# Relay8WatchdogShield.net
KiCad netlist of a schematic drawn in EAGLE
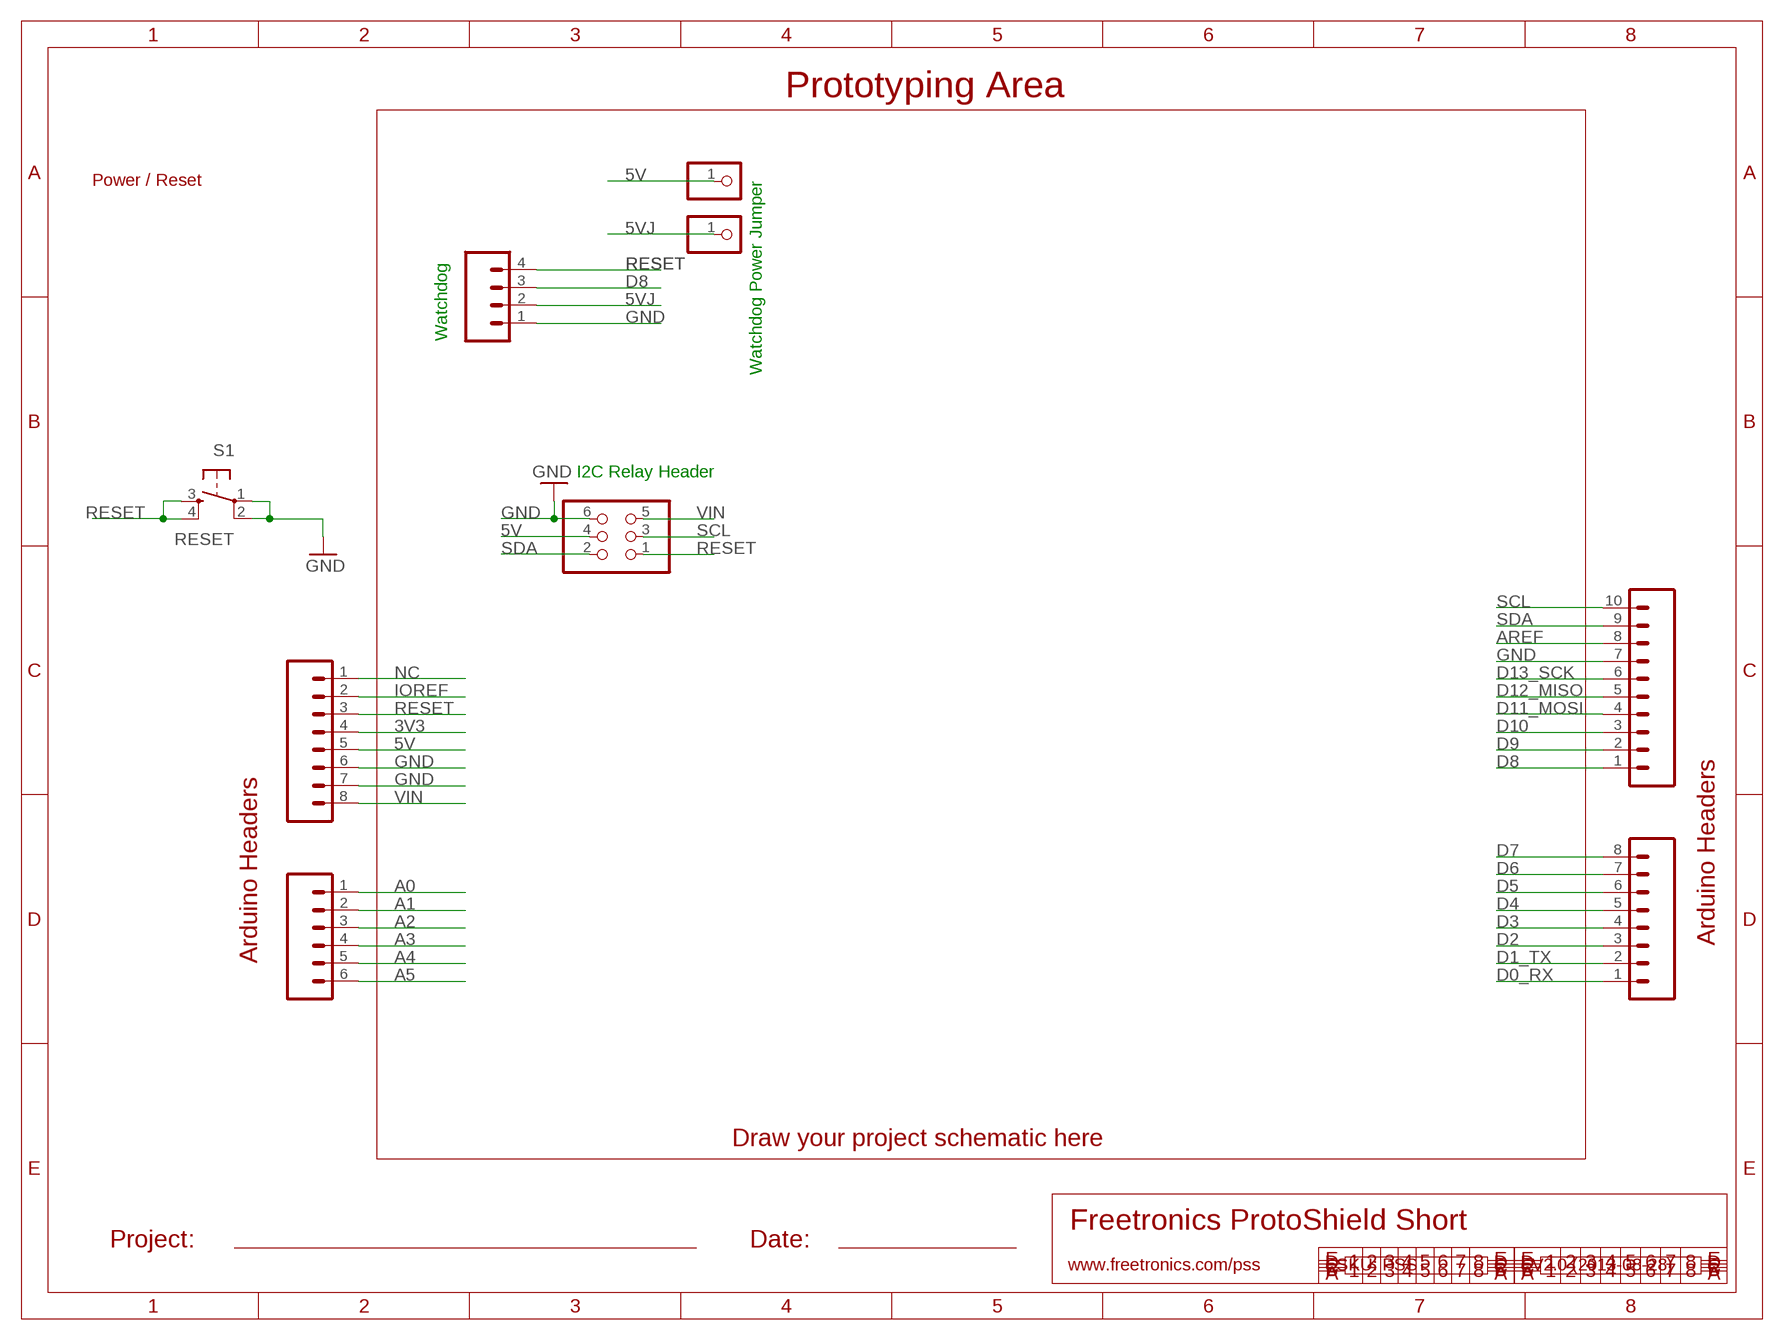
[diagram p0: schematic, sheet 1]

(export (version "E")
  (design (tool "Eeschema 10.0.6"))
  (components
    (comp (ref "J1")
      (value "Digital_0_7")
      (footprint "eagle-import:1X08")
      (libsource (lib "eagle-import") (part "M08"))
    )
    (comp (ref "J2")
      (value "Analog")
      (footprint "eagle-import:1X06")
      (libsource (lib "eagle-import") (part "M06SIP"))
    )
    (comp (ref "J3")
      (value "Digital_8_13")
      (footprint "eagle-import:1X10")
      (libsource (lib "eagle-import") (part "M100.1"))
    )
    (comp (ref "JP1")
      (value "PINHD-1X1")
      (footprint "eagle-import:1X01")
      (libsource (lib "eagle-import") (part "PINHD-1X1"))
    )
    (comp (ref "JP2")
      (value "PINHD-1X1")
      (footprint "eagle-import:1X01")
      (libsource (lib "eagle-import") (part "PINHD-1X1"))
    )
    (comp (ref "JP3")
      (value "FREETRONICS-MASTER-V1_M04PTH")
      (footprint "eagle-import:FREETRONICS-MASTER-V1_1X04")
      (libsource (lib "eagle-import") (part "FREETRONICS-MASTER-V1_M04PTH"))
    )
    (comp (ref "JP4")
      (value "PINHD-2X3")
      (footprint "eagle-import:2X03")
      (libsource (lib "eagle-import") (part "PINHD-2X3"))
    )
    (comp (ref "POWER")
      (value "Power")
      (footprint "eagle-import:1X08")
      (libsource (lib "eagle-import") (part "M08"))
    )
    (comp (ref "S1")
      (value "RESET")
      (footprint "eagle-import:TACTILE-PTH")
      (libsource (lib "eagle-import") (part "TAC_SWITCHPTH"))
    )
  )
  (nets
    (net (code "1") (name "/3V3") (class "Default")
      (node (ref "POWER") (pin "4") (pinfunction "4_4") (pintype "passive"))
    )
    (net (code "2") (name "/5V") (class "Default")
      (node (ref "JP1") (pin "1") (pinfunction "1_1") (pintype "passive"))
      (node (ref "JP4") (pin "4") (pinfunction "4_4") (pintype "passive"))
      (node (ref "POWER") (pin "5") (pinfunction "5_5") (pintype "passive"))
    )
    (net (code "3") (name "/5VJ") (class "Default")
      (node (ref "JP2") (pin "1") (pinfunction "1_1") (pintype "passive"))
      (node (ref "JP3") (pin "2") (pinfunction "2_2") (pintype "passive"))
    )
    (net (code "4") (name "/A0") (class "Default")
      (node (ref "J2") (pin "1") (pinfunction "1_1") (pintype "passive"))
    )
    (net (code "5") (name "/A1") (class "Default")
      (node (ref "J2") (pin "2") (pinfunction "2_2") (pintype "passive"))
    )
    (net (code "6") (name "/A2") (class "Default")
      (node (ref "J2") (pin "3") (pinfunction "3_3") (pintype "passive"))
    )
    (net (code "7") (name "/A3") (class "Default")
      (node (ref "J2") (pin "4") (pinfunction "4_4") (pintype "passive"))
    )
    (net (code "8") (name "/A4") (class "Default")
      (node (ref "J2") (pin "5") (pinfunction "5_5") (pintype "passive"))
    )
    (net (code "9") (name "/A5") (class "Default")
      (node (ref "J2") (pin "6") (pinfunction "6_6") (pintype "passive"))
    )
    (net (code "10") (name "/AREF") (class "Default")
      (node (ref "J3") (pin "8") (pinfunction "8_8") (pintype "passive"))
    )
    (net (code "11") (name "/D0_RX") (class "Default")
      (node (ref "J1") (pin "1") (pinfunction "1_1") (pintype "passive"))
    )
    (net (code "12") (name "/D1_TX") (class "Default")
      (node (ref "J1") (pin "2") (pinfunction "2_2") (pintype "passive"))
    )
    (net (code "13") (name "/D2") (class "Default")
      (node (ref "J1") (pin "3") (pinfunction "3_3") (pintype "passive"))
    )
    (net (code "14") (name "/D3") (class "Default")
      (node (ref "J1") (pin "4") (pinfunction "4_4") (pintype "passive"))
    )
    (net (code "15") (name "/D4") (class "Default")
      (node (ref "J1") (pin "5") (pinfunction "5_5") (pintype "passive"))
    )
    (net (code "16") (name "/D5") (class "Default")
      (node (ref "J1") (pin "6") (pinfunction "6_6") (pintype "passive"))
    )
    (net (code "17") (name "/D6") (class "Default")
      (node (ref "J1") (pin "7") (pinfunction "7_7") (pintype "passive"))
    )
    (net (code "18") (name "/D7") (class "Default")
      (node (ref "J1") (pin "8") (pinfunction "8_8") (pintype "passive"))
    )
    (net (code "19") (name "/D8") (class "Default")
      (node (ref "J3") (pin "1") (pinfunction "1_1") (pintype "passive"))
      (node (ref "JP3") (pin "3") (pinfunction "3_3") (pintype "passive"))
    )
    (net (code "20") (name "/D9") (class "Default")
      (node (ref "J3") (pin "2") (pinfunction "2_2") (pintype "passive"))
    )
    (net (code "21") (name "/D10") (class "Default")
      (node (ref "J3") (pin "3") (pinfunction "3_3") (pintype "passive"))
    )
    (net (code "22") (name "/D11_MOSI") (class "Default")
      (node (ref "J3") (pin "4") (pinfunction "4_4") (pintype "passive"))
    )
    (net (code "23") (name "/D12_MISO") (class "Default")
      (node (ref "J3") (pin "5") (pinfunction "5_5") (pintype "passive"))
    )
    (net (code "24") (name "/D13_SCK") (class "Default")
      (node (ref "J3") (pin "6") (pinfunction "6_6") (pintype "passive"))
    )
    (net (code "25") (name "/IOREF") (class "Default")
      (node (ref "POWER") (pin "2") (pinfunction "2_2") (pintype "passive"))
    )
    (net (code "26") (name "/NC") (class "Default")
      (node (ref "POWER") (pin "1") (pinfunction "1_1") (pintype "passive"))
    )
    (net (code "27") (name "/RESET") (class "Default")
      (node (ref "JP3") (pin "4") (pinfunction "4_4") (pintype "passive"))
      (node (ref "JP4") (pin "1") (pinfunction "1_1") (pintype "passive"))
      (node (ref "POWER") (pin "3") (pinfunction "3_3") (pintype "passive"))
      (node (ref "S1") (pin "3") (pinfunction "3_3") (pintype "passive"))
      (node (ref "S1") (pin "4") (pinfunction "4_4") (pintype "passive"))
    )
    (net (code "28") (name "/SCL") (class "Default")
      (node (ref "J3") (pin "10") (pinfunction "10_10") (pintype "passive"))
      (node (ref "JP4") (pin "3") (pinfunction "3_3") (pintype "passive"))
    )
    (net (code "29") (name "/SDA") (class "Default")
      (node (ref "J3") (pin "9") (pinfunction "9_9") (pintype "passive"))
      (node (ref "JP4") (pin "2") (pinfunction "2_2") (pintype "passive"))
    )
    (net (code "30") (name "/VIN") (class "Default")
      (node (ref "JP4") (pin "5") (pinfunction "5_5") (pintype "passive"))
      (node (ref "POWER") (pin "8") (pinfunction "8_8") (pintype "passive"))
    )
    (net (code "31") (name "GND") (class "Default")
      (node (ref "J3") (pin "7") (pinfunction "7_7") (pintype "passive"))
      (node (ref "JP3") (pin "1") (pinfunction "1_1") (pintype "passive"))
      (node (ref "JP4") (pin "6") (pinfunction "6_6") (pintype "passive"))
      (node (ref "POWER") (pin "6") (pinfunction "6_6") (pintype "passive"))
      (node (ref "POWER") (pin "7") (pinfunction "7_7") (pintype "passive"))
      (node (ref "S1") (pin "1") (pinfunction "1_1") (pintype "passive"))
      (node (ref "S1") (pin "2") (pinfunction "2_2") (pintype "passive"))
    )
  )
)
